# PULSE.net
KiCad netlist of a schematic drawn in Altium Designer
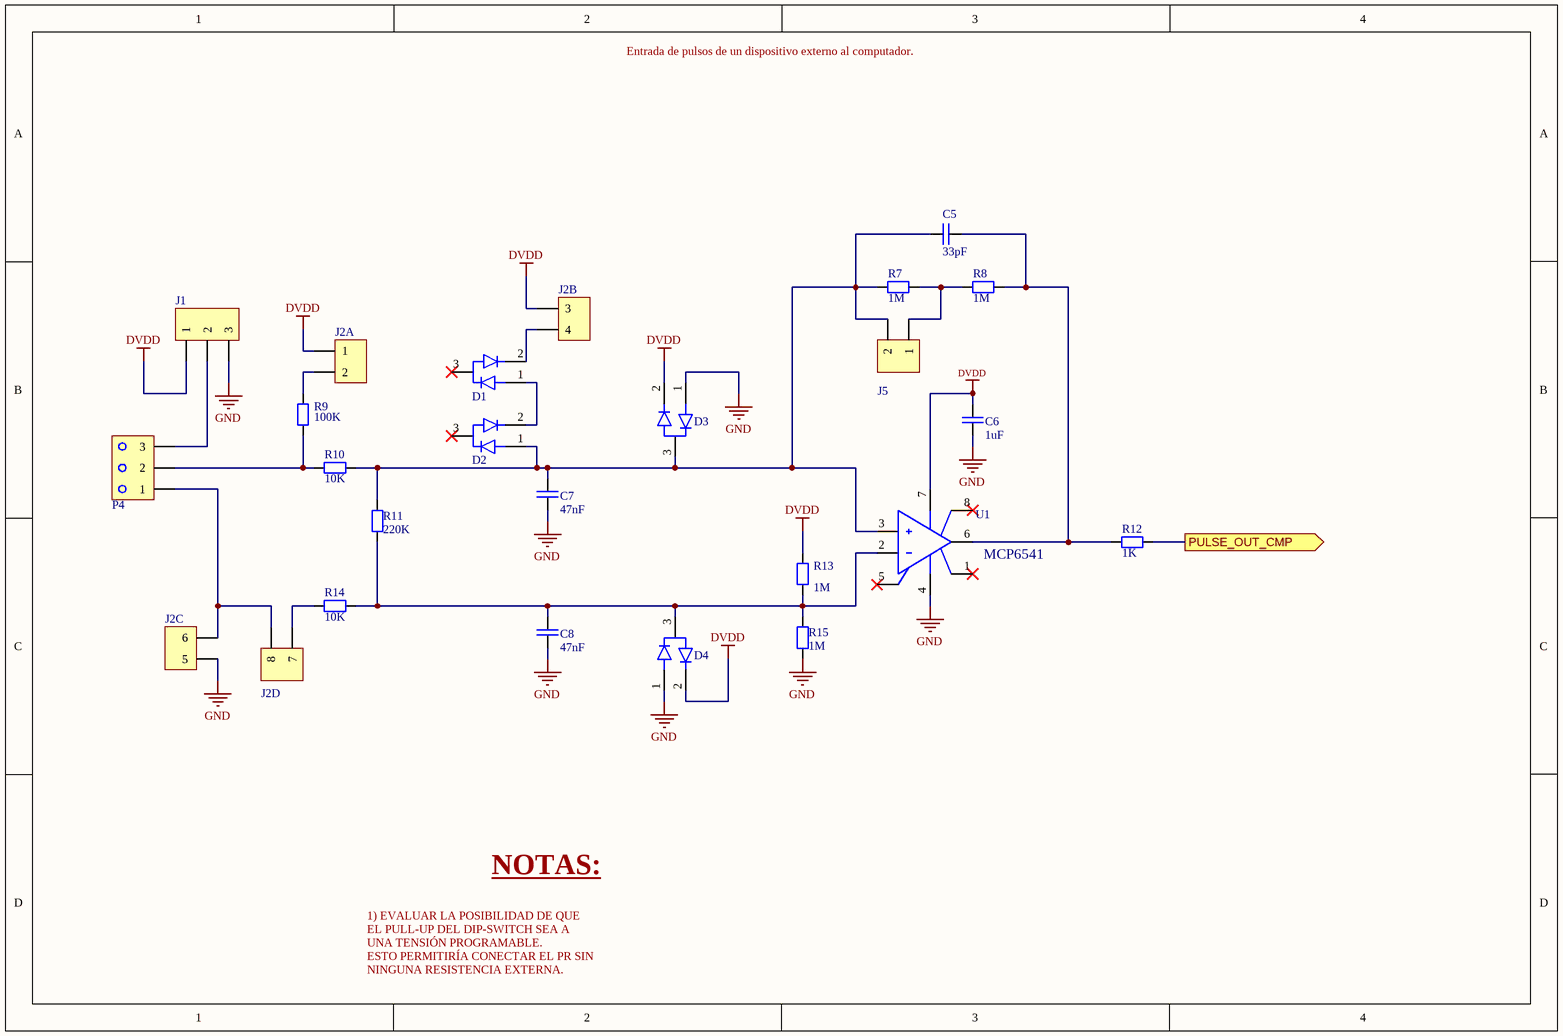
[diagram p0: PULSE.SchDoc]

(export (version "E")
  (design (tool "Eeschema 10.0.6"))
  (components
    (comp (ref "C5")
      (value "33pF")
      (footprint "CAP_SM0805_YAGEOCC2_N")
      (description "CAP 33pF SM0805 NPO 50V YAGEO CC2")
      (fields
        (field (name "MANUFACTURER") "Yageo")
        (field (name "MANUFACTURER PART NUMBER") "CC0805JRNPO9BN330")
      )
      (libsource (lib "Yageo") (part "CC0805JRNPO9BN330"))
    )
    (comp (ref "C6")
      (value "1uF")
      (footprint "CAP_SM0805_YAGEOCC2_N")
      (description "CAP 1uF SM0805 X7R 25V YAGEO CC2")
      (fields
        (field (name "MANUFACTURER") "Yageo")
        (field (name "MANUFACTURER PART NUMBER") "CC0805KKX7R8BB105")
      )
      (libsource (lib "Yageo") (part "CC0805KKX7R8BB105"))
    )
    (comp (ref "C7")
      (value "47nF")
      (footprint "CAP_SM0805_YAGEOCC2_N")
      (description "CAP 47nF SM0805 X7R 25V YAGEO CC2")
      (fields
        (field (name "MANUFACTURER") "Yageo")
        (field (name "MANUFACTURER PART NUMBER") "CC0805KRX7R8BB473")
      )
      (libsource (lib "Yageo") (part "CC0805KRX7R8BB473"))
    )
    (comp (ref "C8")
      (value "47nF")
      (footprint "CAP_SM0805_YAGEOCC2_N")
      (description "CAP 47nF SM0805 X7R 25V YAGEO CC2")
      (fields
        (field (name "MANUFACTURER") "Yageo")
        (field (name "MANUFACTURER PART NUMBER") "CC0805KRX7R8BB473")
      )
      (libsource (lib "Yageo") (part "CC0805KRX7R8BB473"))
    )
    (comp (ref "D1")
      (value "BAV23S")
      (footprint "BAV23S")
      (description "DIODE ARRAY GP 250V 200MA SOT23")
      (fields (field (name "MANUFACTURER") "onsemi"))
      (libsource (lib "diode") (part "BAV23S"))
    )
    (comp (ref "D2")
      (value "BAV23S")
      (footprint "BAV23S")
      (description "DIODE ARRAY GP 250V 200MA SOT23")
      (fields (field (name "MANUFACTURER") "onsemi"))
      (libsource (lib "diode") (part "BAV23S"))
    )
    (comp (ref "D3")
      (value "BAV23S")
      (footprint "BAV23S")
      (description "DIODE ARRAY GP 250V 200MA SOT23")
      (fields (field (name "MANUFACTURER") "onsemi"))
      (libsource (lib "diode") (part "BAV23S"))
    )
    (comp (ref "D4")
      (value "BAV23S")
      (footprint "BAV23S")
      (description "DIODE ARRAY GP 250V 200MA SOT23")
      (fields (field (name "MANUFACTURER") "onsemi"))
      (libsource (lib "diode") (part "BAV23S"))
    )
    (comp (ref "J1")
      (value "~")
      (footprint "HEADER PIN 1X3")
      (description "1 x 3 - Cuttable - true hole  2.54mm - Pb free")
      (fields
        (field (name "MANUFACTURER") "Amphenol ICC")
        (field (name "MANUFACTURER PART NUMBER") "54101-T06-00")
      )
      (libsource (lib "header_pin") (part "54101-T0600LF-03"))
    )
    (comp (ref "J2")
      (value "Usar equivalente")
      (footprint "HEADER PIN 2X4")
      (description "2 x 4  - true hole  2.54mm")
      (fields
        (field (name "MANUFACTURER") "Amphenol ICC")
        (field (name "MANUFACTURER PART NUMBER") "54102-T0604LF")
      )
      (libsource (lib "header_pin") (part "54102-T0604LF-JUMPER"))
    )
    (comp (ref "J5")
      (value "Usar Equivalente")
      (footprint "HEADER PIN 1X2")
      (description "1 x 2 - true hole  2.54mm - Pb free")
      (fields
        (field (name "MANUFACTURER") "Amphenol ICC")
        (field (name "MANUFACTURER PART NUMBER") "54101-T0602LF")
      )
      (libsource (lib "header_pin") (part "54101-T0602LF"))
    )
    (comp (ref "P4")
      (value "WJ15EDGVC-3.81-3P")
      (footprint "HEADER PLUG 3")
      (description "TERM BLOK FEMALE 1X3 3.81MM")
      (fields (field (name "MANUFACTURER") "Ningbo Kangnex Elec"))
      (libsource (lib "plug") (part "WJ15EDGVC-3.81-3P"))
    )
    (comp (ref "R7")
      (value "1M")
      (footprint "RES_SM0805_YAGEORC_N")
      (description "RES 1M SM0805 YAGEO RC_L")
      (fields
        (field (name "MANUFACTURER") "Yageo")
        (field (name "MANUFACTURER PART NUMBER") "RC0805FR-071ML")
      )
      (libsource (lib "") (part "RC0805FR-071ML_1"))
    )
    (comp (ref "R8")
      (value "1M")
      (footprint "RES_SM0805_YAGEORC_N")
      (description "RES 1M SM0805 YAGEO RC_L")
      (fields
        (field (name "MANUFACTURER") "Yageo")
        (field (name "MANUFACTURER PART NUMBER") "RC0805FR-071ML")
      )
      (libsource (lib "") (part "RC0805FR-071ML_1"))
    )
    (comp (ref "R9")
      (value "100K")
      (footprint "RES_SM0805_YAGEORC_N")
      (description "RES 100K SM0805 YAGEO RC_L")
      (fields
        (field (name "MANUFACTURER") "Yageo")
        (field (name "MANUFACTURER PART NUMBER") "RC0805FR-07100KL")
      )
      (libsource (lib "Yageo") (part "RC0805FR-07100KL"))
    )
    (comp (ref "R10")
      (value "10K")
      (footprint "RES_SM0805_YAGEORC_N")
      (description "RES 10K SM0805 YAGEO RC_L")
      (fields
        (field (name "MANUFACTURER") "Yageo")
        (field (name "MANUFACTURER PART NUMBER") "RC0805FR-0710KL")
      )
      (libsource (lib "Yageo") (part "RC0805FR-0710KL"))
    )
    (comp (ref "R11")
      (value "220K")
      (footprint "RES_SM0805_YAGEORC_N")
      (description "RES 220K SM0805 YAGEO RC_L")
      (fields
        (field (name "MANUFACTURER") "Yageo")
        (field (name "MANUFACTURER PART NUMBER") "RC0805FR-07220KL")
      )
      (libsource (lib "Yageo") (part "RC0805FR-07220KL"))
    )
    (comp (ref "R12")
      (value "1K")
      (footprint "RES_SM0805_YAGEORC_N")
      (description "RES 1K SM0805 YAGEO RC_L")
      (fields
        (field (name "MANUFACTURER") "Yageo")
        (field (name "MANUFACTURER PART NUMBER") "RC0805FR-071KL")
      )
      (libsource (lib "Yageo") (part "RC0805FR-071KL"))
    )
    (comp (ref "R13")
      (value "1M")
      (footprint "RES_SM0805_YAGEORC_N")
      (description "RES 1M SM0805 YAGEO RC_L")
      (fields
        (field (name "MANUFACTURER") "Yageo")
        (field (name "MANUFACTURER PART NUMBER") "RC0805FR-071ML")
      )
      (libsource (lib "Yageo") (part "RC0805FR-071ML"))
    )
    (comp (ref "R14")
      (value "10K")
      (footprint "RES_SM0805_YAGEORC_N")
      (description "RES 10K SM0805 YAGEO RC_L")
      (fields
        (field (name "MANUFACTURER") "Yageo")
        (field (name "MANUFACTURER PART NUMBER") "RC0805FR-0710KL")
      )
      (libsource (lib "Yageo") (part "RC0805FR-0710KL"))
    )
    (comp (ref "R15")
      (value "1M")
      (footprint "RES_SM0805_YAGEORC_N")
      (description "RES 1M SM0805 YAGEO RC_L")
      (fields
        (field (name "MANUFACTURER") "Yageo")
        (field (name "MANUFACTURER PART NUMBER") "RC0805FR-071ML")
      )
      (libsource (lib "Yageo") (part "RC0805FR-071ML"))
    )
    (comp (ref "U1")
      (value "MCP6541")
      (footprint "MCP6541-E/SN")
      (description "IC COMP PP I/O SNGL 1.6V 8SOIC")
      (fields
        (field (name "MANUFACTURER") "Microchip Tech")
        (field (name "MANUFACTURER PART NUMBER") "MCP6541-E/SN")
      )
      (libsource (lib "OP_Amps") (part "MCP6541-E/SN"))
    )
  )
  (nets
    (net (code "1") (name "/PULSE_OUT_CMP") (class "Default")
      (node (ref "R12") (pin "2") (pintype "passive"))
    )
    (net (code "2") (name "DVDD") (class "Default")
      (node (ref "C6") (pin "1") (pintype "passive"))
      (node (ref "D3") (pin "2") (pinfunction "2_2") (pintype "passive"))
      (node (ref "D4") (pin "2") (pinfunction "2_2") (pintype "passive"))
      (node (ref "J1") (pin "1") (pinfunction "1_1") (pintype "passive"))
      (node (ref "J2") (pin "1") (pinfunction "1_1") (pintype "passive"))
      (node (ref "J2") (pin "3") (pinfunction "3_3") (pintype "passive"))
      (node (ref "R13") (pin "2") (pintype "passive"))
      (node (ref "U1") (pin "7") (pinfunction "V+_7") (pintype "power_in"))
    )
    (net (code "3") (name "GND") (class "Default")
      (node (ref "C6") (pin "2") (pintype "passive"))
      (node (ref "C7") (pin "2") (pintype "passive"))
      (node (ref "C8") (pin "2") (pintype "passive"))
      (node (ref "D3") (pin "1") (pinfunction "1_1") (pintype "passive"))
      (node (ref "D4") (pin "1") (pinfunction "1_1") (pintype "passive"))
      (node (ref "J1") (pin "3") (pinfunction "3_3") (pintype "passive"))
      (node (ref "J2") (pin "5") (pinfunction "5_5") (pintype "passive"))
      (node (ref "R15") (pin "1") (pintype "passive"))
      (node (ref "U1") (pin "4") (pinfunction "V-_4") (pintype "power_in"))
    )
    (net (code "4") (name "Net-(D1-Pad1)") (class "Default")
      (node (ref "D1") (pin "1") (pinfunction "1_1") (pintype "passive"))
      (node (ref "D2") (pin "2") (pinfunction "2_2") (pintype "passive"))
    )
    (net (code "5") (name "Net-(D1-Pad2)") (class "Default")
      (node (ref "D1") (pin "2") (pinfunction "2_2") (pintype "passive"))
      (node (ref "J2") (pin "4") (pinfunction "4_4") (pintype "passive"))
    )
    (net (code "6") (name "Net-(J1-Pad2)") (class "Default")
      (node (ref "J1") (pin "2") (pinfunction "2_2") (pintype "passive"))
      (node (ref "P4") (pin "3") (pinfunction "3_3") (pintype "passive"))
    )
    (net (code "7") (name "Net-(J2-Pad2)") (class "Default")
      (node (ref "J2") (pin "2") (pinfunction "2_2") (pintype "passive"))
      (node (ref "R9") (pin "2") (pintype "passive"))
    )
    (net (code "8") (name "Net-(J2-Pad6)") (class "Default")
      (node (ref "J2") (pin "6") (pinfunction "6_6") (pintype "passive"))
      (node (ref "J2") (pin "8") (pinfunction "8_8") (pintype "passive"))
      (node (ref "P4") (pin "1") (pinfunction "1_1") (pintype "passive"))
    )
    (net (code "9") (name "Net-(J2-Pad7)") (class "Default")
      (node (ref "J2") (pin "7") (pinfunction "7_7") (pintype "passive"))
      (node (ref "R14") (pin "1") (pintype "passive"))
    )
    (net (code "10") (name "Net-(J5-Pad1)") (class "Default")
      (node (ref "J5") (pin "1") (pinfunction "1_1") (pintype "passive"))
      (node (ref "R7") (pin "2") (pintype "passive"))
      (node (ref "R8") (pin "1") (pintype "passive"))
    )
    (net (code "11") (name "Net-(P4-Pad2)") (class "Default")
      (node (ref "P4") (pin "2") (pinfunction "2_2") (pintype "passive"))
      (node (ref "R10") (pin "1") (pintype "passive"))
      (node (ref "R9") (pin "1") (pintype "passive"))
    )
    (net (code "12") (name "Net-(U1-IN+)") (class "Default")
      (node (ref "C5") (pin "1") (pintype "passive"))
      (node (ref "C7") (pin "1") (pintype "passive"))
      (node (ref "D2") (pin "1") (pinfunction "1_1") (pintype "passive"))
      (node (ref "D3") (pin "3") (pinfunction "3_3") (pintype "passive"))
      (node (ref "J5") (pin "2") (pinfunction "2_2") (pintype "passive"))
      (node (ref "R10") (pin "2") (pintype "passive"))
      (node (ref "R11") (pin "2") (pintype "passive"))
      (node (ref "R7") (pin "1") (pintype "passive"))
      (node (ref "U1") (pin "3") (pinfunction "IN+_3") (pintype "passive"))
    )
    (net (code "13") (name "Net-(U1-IN-)") (class "Default")
      (node (ref "C8") (pin "1") (pintype "passive"))
      (node (ref "D4") (pin "3") (pinfunction "3_3") (pintype "passive"))
      (node (ref "R11") (pin "1") (pintype "passive"))
      (node (ref "R13") (pin "1") (pintype "passive"))
      (node (ref "R14") (pin "2") (pintype "passive"))
      (node (ref "R15") (pin "2") (pintype "passive"))
      (node (ref "U1") (pin "2") (pinfunction "IN-_2") (pintype "passive"))
    )
    (net (code "14") (name "Net-(U1-OUT)") (class "Default")
      (node (ref "C5") (pin "2") (pintype "passive"))
      (node (ref "R12") (pin "1") (pintype "passive"))
      (node (ref "R8") (pin "2") (pintype "passive"))
      (node (ref "U1") (pin "6") (pinfunction "OUT_6") (pintype "passive"))
    )
    (net (code "15") (name "unconnected-(D1-Pad3)") (class "Default")
      (node (ref "D1") (pin "3") (pinfunction "3_3") (pintype "passive+no_connect"))
    )
    (net (code "16") (name "unconnected-(D2-Pad3)") (class "Default")
      (node (ref "D2") (pin "3") (pinfunction "3_3") (pintype "passive+no_connect"))
    )
    (net (code "17") (name "unconnected-(U1-OS_NUL-Pad1)") (class "Default")
      (node (ref "U1") (pin "1") (pinfunction "OS_NUL_1") (pintype "passive+no_connect"))
    )
    (net (code "18") (name "unconnected-(U1-OS_NUL-Pad5)") (class "Default")
      (node (ref "U1") (pin "5") (pinfunction "OS_NUL_5") (pintype "passive+no_connect"))
    )
    (net (code "19") (name "unconnected-(U1-TAB-Pad8)") (class "Default")
      (node (ref "U1") (pin "8") (pinfunction "TAB_8") (pintype "passive+no_connect"))
    )
  )
)
